# Input.net
KiCad netlist of a schematic drawn in EAGLE
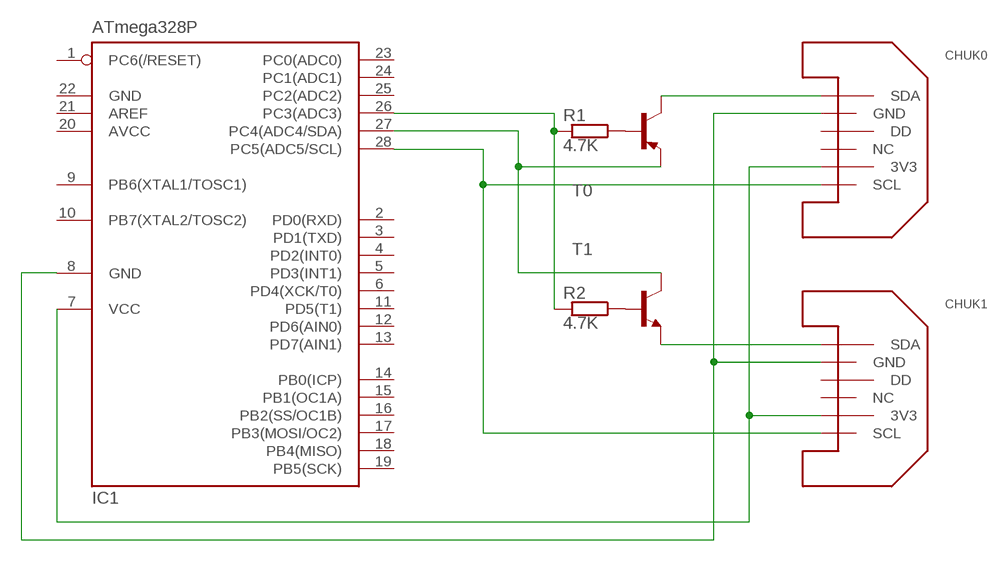
[diagram p0: schematic, sheet 1]

(export (version "E")
  (design (tool "Eeschema 10.0.6"))
  (components
    (comp (ref "CHUK0")
      (value "WII-NUNCHUK")
      (footprint "eagle-import:WII-NUNCHUK")
      (libsource (lib "eagle-import") (part "WII-NUNCHUK"))
    )
    (comp (ref "CHUK1")
      (value "WII-NUNCHUK")
      (footprint "eagle-import:WII-NUNCHUK")
      (libsource (lib "eagle-import") (part "WII-NUNCHUK"))
    )
    (comp (ref "IC1")
      (value "ATmega328P")
      (footprint "eagle-import:DIL28-3")
      (libsource (lib "eagle-import") (part "MEGA8-P"))
    )
    (comp (ref "R1")
      (value "4.7K")
      (footprint "eagle-import:BVS")
      (libsource (lib "eagle-import") (part "BVS"))
    )
    (comp (ref "R2")
      (value "4.7K")
      (footprint "eagle-import:BVS")
      (libsource (lib "eagle-import") (part "BVS"))
    )
    (comp (ref "T0")
      (value "-PNP-SOT23-BCE")
      (footprint "eagle-import:SOT23-BCE")
      (libsource (lib "eagle-import") (part "-PNP-SOT23-BCE"))
    )
    (comp (ref "T1")
      (value "-NPN-SOT23-EBC")
      (footprint "eagle-import:SOT23-EBC")
      (libsource (lib "eagle-import") (part "-NPN-SOT23-EBC"))
    )
  )
  (nets
    (net (code "1") (name "/AVCC") (class "Default")
      (node (ref "IC1") (pin "20") (pinfunction "AVCC_20") (pintype "power_in"))
    )
    (net (code "2") (name "/GND") (class "Default")
      (node (ref "IC1") (pin "22") (pinfunction "GND_22") (pintype "power_in"))
    )
    (net (code "3") (name "Net-(CHUK0-PadGND)") (class "Default")
      (node (ref "CHUK0") (pin "GND") (pinfunction "GND_GND") (pintype "bidirectional"))
      (node (ref "CHUK1") (pin "GND") (pinfunction "GND_GND") (pintype "bidirectional"))
      (node (ref "IC1") (pin "8") (pinfunction "GND_8") (pintype "power_in"))
    )
    (net (code "4") (name "Net-(CHUK0-PadSDA)") (class "Default")
      (node (ref "CHUK0") (pin "SDA") (pinfunction "SDA_SDA") (pintype "bidirectional"))
      (node (ref "T0") (pin "C") (pinfunction "C_C") (pintype "passive"))
    )
    (net (code "5") (name "Net-(CHUK1-PadSDA)") (class "Default")
      (node (ref "CHUK1") (pin "SDA") (pinfunction "SDA_SDA") (pintype "bidirectional"))
      (node (ref "T1") (pin "E") (pinfunction "E_E") (pintype "passive"))
    )
    (net (code "6") (name "Net-(IC1-PC3(ADC3))") (class "Default")
      (node (ref "IC1") (pin "26") (pinfunction "PC3(ADC3)_26") (pintype "bidirectional"))
      (node (ref "R1") (pin "2") (pinfunction "2_2") (pintype "passive"))
      (node (ref "R2") (pin "2") (pinfunction "2_2") (pintype "passive"))
    )
    (net (code "7") (name "Net-(IC1-PC4(ADC4{slash}SDA))") (class "Default")
      (node (ref "IC1") (pin "27") (pinfunction "PC4(ADC4/SDA)_27") (pintype "bidirectional"))
      (node (ref "T0") (pin "E") (pinfunction "E_E") (pintype "passive"))
      (node (ref "T1") (pin "C") (pinfunction "C_C") (pintype "passive"))
    )
    (net (code "8") (name "Net-(IC1-PC5(ADC5{slash}SCL))") (class "Default")
      (node (ref "CHUK0") (pin "SCL") (pinfunction "SCL_SCL") (pintype "bidirectional"))
      (node (ref "CHUK1") (pin "SCL") (pinfunction "SCL_SCL") (pintype "bidirectional"))
      (node (ref "IC1") (pin "28") (pinfunction "PC5(ADC5/SCL)_28") (pintype "bidirectional"))
    )
    (net (code "9") (name "Net-(IC1-VCC)") (class "Default")
      (node (ref "CHUK0") (pin "3V3") (pinfunction "3V3_3V3") (pintype "bidirectional"))
      (node (ref "CHUK1") (pin "3V3") (pinfunction "3V3_3V3") (pintype "bidirectional"))
      (node (ref "IC1") (pin "7") (pinfunction "VCC_7") (pintype "power_in"))
    )
    (net (code "10") (name "Net-(R1-Pad1)") (class "Default")
      (node (ref "R1") (pin "1") (pinfunction "1_1") (pintype "passive"))
      (node (ref "T0") (pin "B") (pinfunction "B_B") (pintype "passive"))
    )
    (net (code "11") (name "Net-(R2-Pad1)") (class "Default")
      (node (ref "R2") (pin "1") (pinfunction "1_1") (pintype "passive"))
      (node (ref "T1") (pin "B") (pinfunction "B_B") (pintype "passive"))
    )
    (net (code "12") (name "unconnected-(CHUK0-PadDD)") (class "Default")
      (node (ref "CHUK0") (pin "DD") (pinfunction "DD_DD") (pintype "bidirectional"))
    )
    (net (code "13") (name "unconnected-(CHUK0-PadNC)") (class "Default")
      (node (ref "CHUK0") (pin "NC") (pinfunction "NC_NC") (pintype "bidirectional"))
    )
    (net (code "14") (name "unconnected-(CHUK1-PadDD)") (class "Default")
      (node (ref "CHUK1") (pin "DD") (pinfunction "DD_DD") (pintype "bidirectional"))
    )
    (net (code "15") (name "unconnected-(CHUK1-PadNC)") (class "Default")
      (node (ref "CHUK1") (pin "NC") (pinfunction "NC_NC") (pintype "bidirectional"))
    )
    (net (code "16") (name "unconnected-(IC1-AREF-Pad21)") (class "Default")
      (node (ref "IC1") (pin "21") (pinfunction "AREF_21") (pintype "passive"))
    )
    (net (code "17") (name "unconnected-(IC1-PB0(ICP)-Pad14)") (class "Default")
      (node (ref "IC1") (pin "14") (pinfunction "PB0(ICP)_14") (pintype "bidirectional"))
    )
    (net (code "18") (name "unconnected-(IC1-PB1(OC1A)-Pad15)") (class "Default")
      (node (ref "IC1") (pin "15") (pinfunction "PB1(OC1A)_15") (pintype "bidirectional"))
    )
    (net (code "19") (name "unconnected-(IC1-PB2(SS{slash}OC1B)-Pad16)") (class "Default")
      (node (ref "IC1") (pin "16") (pinfunction "PB2(SS/OC1B)_16") (pintype "bidirectional"))
    )
    (net (code "20") (name "unconnected-(IC1-PB3(MOSI{slash}OC2)-Pad17)") (class "Default")
      (node (ref "IC1") (pin "17") (pinfunction "PB3(MOSI/OC2)_17") (pintype "bidirectional"))
    )
    (net (code "21") (name "unconnected-(IC1-PB4(MISO)-Pad18)") (class "Default")
      (node (ref "IC1") (pin "18") (pinfunction "PB4(MISO)_18") (pintype "bidirectional"))
    )
    (net (code "22") (name "unconnected-(IC1-PB5(SCK)-Pad19)") (class "Default")
      (node (ref "IC1") (pin "19") (pinfunction "PB5(SCK)_19") (pintype "bidirectional"))
    )
    (net (code "23") (name "unconnected-(IC1-PB6(XTAL1{slash}TOSC1)-Pad9)") (class "Default")
      (node (ref "IC1") (pin "9") (pinfunction "PB6(XTAL1/TOSC1)_9") (pintype "bidirectional"))
    )
    (net (code "24") (name "unconnected-(IC1-PB7(XTAL2{slash}TOSC2)-Pad10)") (class "Default")
      (node (ref "IC1") (pin "10") (pinfunction "PB7(XTAL2/TOSC2)_10") (pintype "bidirectional"))
    )
    (net (code "25") (name "unconnected-(IC1-PC0(ADC0)-Pad23)") (class "Default")
      (node (ref "IC1") (pin "23") (pinfunction "PC0(ADC0)_23") (pintype "bidirectional"))
    )
    (net (code "26") (name "unconnected-(IC1-PC1(ADC1)-Pad24)") (class "Default")
      (node (ref "IC1") (pin "24") (pinfunction "PC1(ADC1)_24") (pintype "bidirectional"))
    )
    (net (code "27") (name "unconnected-(IC1-PC2(ADC2)-Pad25)") (class "Default")
      (node (ref "IC1") (pin "25") (pinfunction "PC2(ADC2)_25") (pintype "bidirectional"))
    )
    (net (code "28") (name "unconnected-(IC1-PC6({slash}RESET)-Pad1)") (class "Default")
      (node (ref "IC1") (pin "1") (pinfunction "PC6(/RESET)_1") (pintype "bidirectional"))
    )
    (net (code "29") (name "unconnected-(IC1-PD0(RXD)-Pad2)") (class "Default")
      (node (ref "IC1") (pin "2") (pinfunction "PD0(RXD)_2") (pintype "bidirectional"))
    )
    (net (code "30") (name "unconnected-(IC1-PD1(TXD)-Pad3)") (class "Default")
      (node (ref "IC1") (pin "3") (pinfunction "PD1(TXD)_3") (pintype "bidirectional"))
    )
    (net (code "31") (name "unconnected-(IC1-PD2(INT0)-Pad4)") (class "Default")
      (node (ref "IC1") (pin "4") (pinfunction "PD2(INT0)_4") (pintype "bidirectional"))
    )
    (net (code "32") (name "unconnected-(IC1-PD3(INT1)-Pad5)") (class "Default")
      (node (ref "IC1") (pin "5") (pinfunction "PD3(INT1)_5") (pintype "bidirectional"))
    )
    (net (code "33") (name "unconnected-(IC1-PD4(XCK{slash}T0)-Pad6)") (class "Default")
      (node (ref "IC1") (pin "6") (pinfunction "PD4(XCK/T0)_6") (pintype "bidirectional"))
    )
    (net (code "34") (name "unconnected-(IC1-PD5(T1)-Pad11)") (class "Default")
      (node (ref "IC1") (pin "11") (pinfunction "PD5(T1)_11") (pintype "bidirectional"))
    )
    (net (code "35") (name "unconnected-(IC1-PD6(AIN0)-Pad12)") (class "Default")
      (node (ref "IC1") (pin "12") (pinfunction "PD6(AIN0)_12") (pintype "bidirectional"))
    )
    (net (code "36") (name "unconnected-(IC1-PD7(AIN1)-Pad13)") (class "Default")
      (node (ref "IC1") (pin "13") (pinfunction "PD7(AIN1)_13") (pintype "bidirectional"))
    )
  )
)
